# Peripherals.net
KiCad netlist of a schematic drawn in Altium Designer
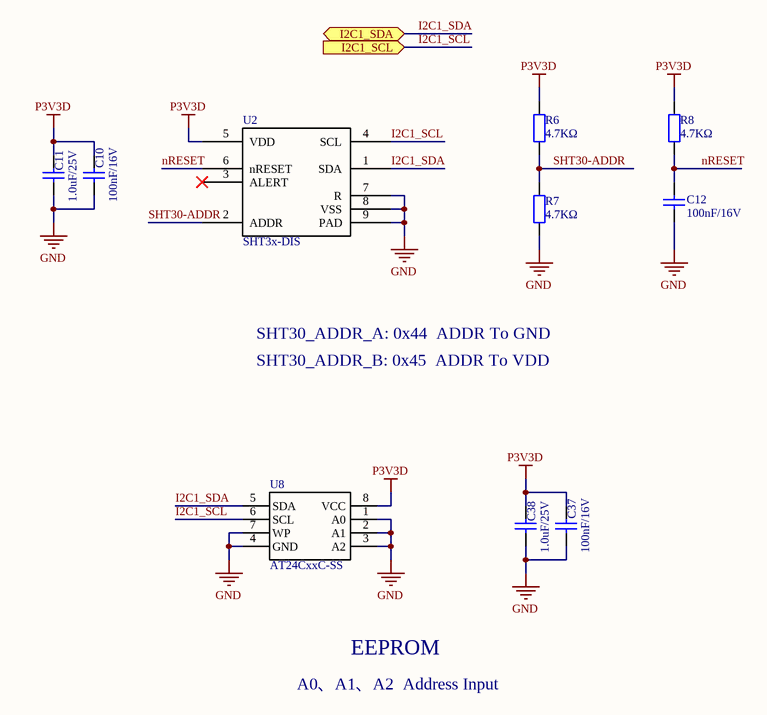
[diagram p0: Peripherals.SchDoc]

(export (version "E")
  (design (tool "Eeschema 10.0.6"))
  (components
    (comp (ref "C10")
      (value "100nF/16V")
      (footprint "0402_C")
      (description "贴片电容")
      (libsource (lib "Miscellaneous Devices LC") (part "0402 100nF (104) 10% 16V"))
    )
    (comp (ref "C11")
      (value "1.0uF/25V")
      (footprint "0402_C")
      (description "贴片电容")
      (libsource (lib "Miscellaneous Devices LC") (part "0402 1.0uF (105) 10% 25V"))
    )
    (comp (ref "C12")
      (value "100nF/16V")
      (footprint "0402_C")
      (description "贴片电容")
      (libsource (lib "Miscellaneous Devices LC") (part "0402 100nF (104) 10% 16V"))
    )
    (comp (ref "C37")
      (value "100nF/16V")
      (footprint "0402_C")
      (description "贴片电容")
      (libsource (lib "Miscellaneous Devices LC") (part "0402 100nF (104) 10% 16V"))
    )
    (comp (ref "C38")
      (value "1.0uF/25V")
      (footprint "0402_C")
      (description "贴片电容")
      (libsource (lib "Miscellaneous Devices LC") (part "0402 1.0uF (105) 10% 25V"))
    )
    (comp (ref "R6")
      (value "4.7KΩ")
      (footprint "0402_R")
      (description "贴片电阻")
      (libsource (lib "Miscellaneous Devices LC") (part "0402 4.7KΩ (4701) 1%"))
    )
    (comp (ref "R7")
      (value "4.7KΩ")
      (footprint "0402_R")
      (description "贴片电阻")
      (libsource (lib "Miscellaneous Devices LC") (part "0402 4.7KΩ (4701) 1%"))
    )
    (comp (ref "R8")
      (value "4.7KΩ")
      (footprint "0402_R")
      (description "贴片电阻")
      (libsource (lib "Miscellaneous Devices LC") (part "0402 4.7KΩ (4701) 1%"))
    )
    (comp (ref "U2")
      (value "SHT3x-DIS")
      (footprint "SHT3x-DIS_SEN")
      (description "Humidity and Temperature Sensor")
      (fields
        (field (name "MANUFACTURER_PART_NUMBER") "SHT30-DIS-F2.5KS")
        (field (name "COPYRIGHT") "Copyright (C) 2018 Accelerated Designs. All rights reserved")
      )
      (libsource (lib "IC") (part "SHT3x-DIS"))
    )
    (comp (ref "U8")
      (value "AT24CxxC-SS")
      (footprint "SOIC-8-39mm")
      (description "Serial EEPROM")
      (libsource (lib "IC") (part "AT24CxxC-SS"))
    )
  )
  (nets
    (net (code "1") (name "/I2C1_SCL") (class "Default")
      (node (ref "U2") (pin "4") (pinfunction "SCL_4") (pintype "passive"))
      (node (ref "U8") (pin "6") (pinfunction "SCL_6") (pintype "passive"))
    )
    (net (code "2") (name "/I2C1_SDA") (class "Default")
      (node (ref "U2") (pin "1") (pinfunction "SDA_1") (pintype "passive"))
      (node (ref "U8") (pin "5") (pinfunction "SDA_5") (pintype "passive"))
    )
    (net (code "3") (name "/SHT30-ADDR") (class "Default")
      (node (ref "R6") (pin "1") (pinfunction "1_1") (pintype "passive"))
      (node (ref "R7") (pin "2") (pinfunction "2_2") (pintype "passive"))
      (node (ref "U2") (pin "2") (pinfunction "ADDR_2") (pintype "passive"))
    )
    (net (code "4") (name "/nRESET") (class "Default")
      (node (ref "C12") (pin "2") (pinfunction "2_2") (pintype "passive"))
      (node (ref "R8") (pin "1") (pinfunction "1_1") (pintype "passive"))
      (node (ref "U2") (pin "6") (pinfunction "nRESET_6") (pintype "passive"))
    )
    (net (code "5") (name "GND") (class "Default")
      (node (ref "C10") (pin "1") (pinfunction "1_1") (pintype "passive"))
      (node (ref "C11") (pin "1") (pinfunction "1_1") (pintype "passive"))
      (node (ref "C12") (pin "1") (pinfunction "1_1") (pintype "passive"))
      (node (ref "C37") (pin "1") (pinfunction "1_1") (pintype "passive"))
      (node (ref "C38") (pin "1") (pinfunction "1_1") (pintype "passive"))
      (node (ref "R7") (pin "1") (pinfunction "1_1") (pintype "passive"))
      (node (ref "U2") (pin "7") (pinfunction "R_7") (pintype "passive"))
      (node (ref "U2") (pin "8") (pinfunction "VSS_8") (pintype "passive"))
      (node (ref "U2") (pin "9") (pinfunction "PAD_9") (pintype "passive"))
      (node (ref "U8") (pin "1") (pinfunction "A0_1") (pintype "passive"))
      (node (ref "U8") (pin "2") (pinfunction "A1_2") (pintype "passive"))
      (node (ref "U8") (pin "3") (pinfunction "A2_3") (pintype "passive"))
      (node (ref "U8") (pin "4") (pinfunction "GND_4") (pintype "passive"))
      (node (ref "U8") (pin "7") (pinfunction "WP_7") (pintype "passive"))
    )
    (net (code "6") (name "P3V3D") (class "Default")
      (node (ref "C10") (pin "2") (pinfunction "2_2") (pintype "passive"))
      (node (ref "C11") (pin "2") (pinfunction "2_2") (pintype "passive"))
      (node (ref "C37") (pin "2") (pinfunction "2_2") (pintype "passive"))
      (node (ref "C38") (pin "2") (pinfunction "2_2") (pintype "passive"))
      (node (ref "R6") (pin "2") (pinfunction "2_2") (pintype "passive"))
      (node (ref "R8") (pin "2") (pinfunction "2_2") (pintype "passive"))
      (node (ref "U2") (pin "5") (pinfunction "VDD_5") (pintype "power_in"))
      (node (ref "U8") (pin "8") (pinfunction "VCC_8") (pintype "passive"))
    )
    (net (code "7") (name "unconnected-(U2-ALERT-Pad3)") (class "Default")
      (node (ref "U2") (pin "3") (pinfunction "ALERT_3") (pintype "passive+no_connect"))
    )
  )
)
